# tACS_precision_revised.net
KiCad netlist of a schematic drawn in EAGLE
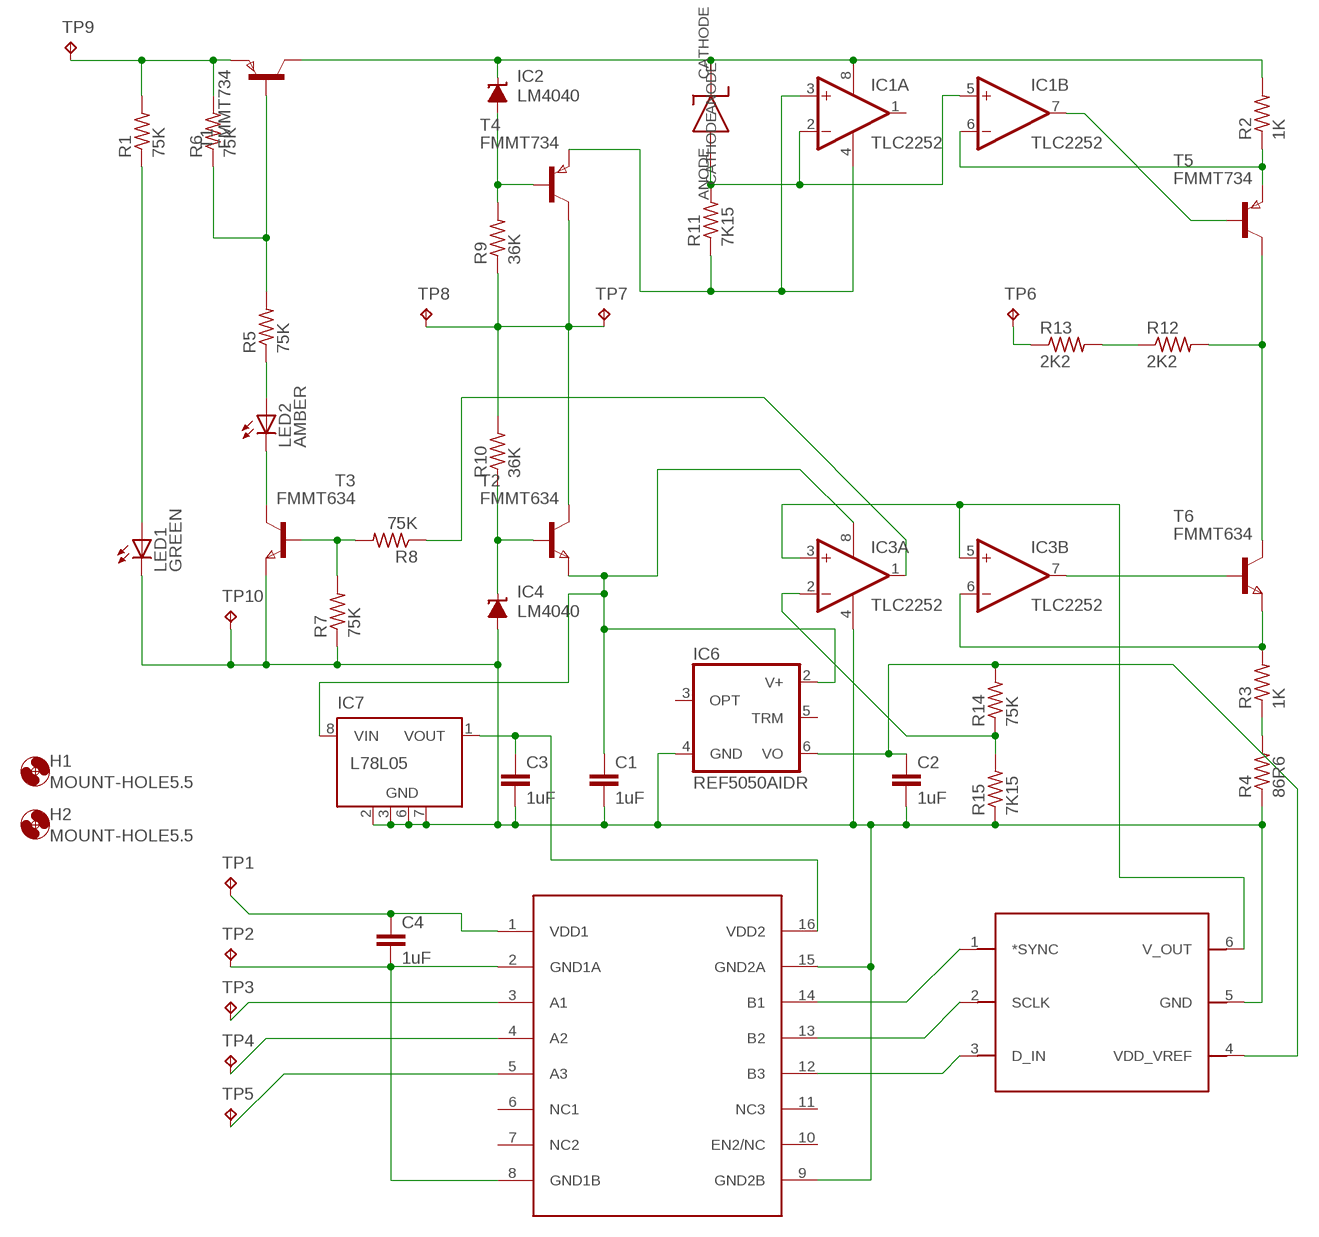
[diagram p0: schematic, sheet 1]

(export (version "E")
  (design (tool "Eeschema 10.0.6"))
  (components
    (comp (ref "C1")
      (value "1uF")
      (footprint "eagle-import:C1608")
      (libsource (lib "eagle-import") (part "C-EUC1608"))
    )
    (comp (ref "C2")
      (value "1uF")
      (footprint "eagle-import:C1608")
      (libsource (lib "eagle-import") (part "C-EUC1608"))
    )
    (comp (ref "C3")
      (value "1uF")
      (footprint "eagle-import:C1608")
      (libsource (lib "eagle-import") (part "C-EUC1608"))
    )
    (comp (ref "C4")
      (value "1uF")
      (footprint "eagle-import:C1608")
      (libsource (lib "eagle-import") (part "C-EUC1608"))
    )
    (comp (ref "H1")
      (value "MOUNT-HOLE5.5")
      (footprint "eagle-import:5,5")
      (libsource (lib "eagle-import") (part "MOUNT-HOLE5.5"))
    )
    (comp (ref "H2")
      (value "MOUNT-HOLE5.5")
      (footprint "eagle-import:5,5")
      (libsource (lib "eagle-import") (part "MOUNT-HOLE5.5"))
    )
    (comp (ref "IC1")
      (value "TLC2252")
      (footprint "eagle-import:SO08")
      (libsource (lib "eagle-import") (part "TLC272D"))
    )
    (comp (ref "IC2")
      (value "LM4040")
      (footprint "eagle-import:DBZ_R-PDSO-G3")
      (fields (field (name "MPN") "LM4041A12IDBZR"))
      (libsource (lib "eagle-import") (part "LM4041DBZA12"))
    )
    (comp (ref "IC3")
      (value "TLC2252")
      (footprint "eagle-import:SO08")
      (libsource (lib "eagle-import") (part "TLC272D"))
    )
    (comp (ref "IC4")
      (value "LM4040")
      (footprint "eagle-import:DBZ_R-PDSO-G3")
      (fields (field (name "MPN") "LM4041A12IDBZR"))
      (libsource (lib "eagle-import") (part "LM4041DBZA12"))
    )
    (comp (ref "IC6")
      (value "REF5050AIDR")
      (footprint "eagle-import:SO08")
      (libsource (lib "eagle-import") (part "REF03D"))
    )
    (comp (ref "IC7")
      (value "L78L05")
      (footprint "eagle-import:SO08")
      (libsource (lib "eagle-import") (part "78LSMD05"))
    )
    (comp (ref "LED1")
      (value "GREEN")
      (footprint "eagle-import:SML0603")
      (libsource (lib "eagle-import") (part "LEDSML0603"))
    )
    (comp (ref "LED2")
      (value "AMBER")
      (footprint "eagle-import:SML1206")
      (libsource (lib "eagle-import") (part "LEDSML1206"))
    )
    (comp (ref "R1")
      (value "75K")
      (footprint "eagle-import:R0603")
      (libsource (lib "eagle-import") (part "R-US_R0603"))
    )
    (comp (ref "R2")
      (value "1K")
      (footprint "eagle-import:R0603")
      (libsource (lib "eagle-import") (part "R-US_R0603"))
    )
    (comp (ref "R3")
      (value "1K")
      (footprint "eagle-import:R0603")
      (libsource (lib "eagle-import") (part "R-US_R0603"))
    )
    (comp (ref "R4")
      (value "86R6")
      (footprint "eagle-import:R0603")
      (libsource (lib "eagle-import") (part "R-US_R0603"))
    )
    (comp (ref "R5")
      (value "75K")
      (footprint "eagle-import:R0603")
      (libsource (lib "eagle-import") (part "R-US_R0603"))
    )
    (comp (ref "R6")
      (value "75K")
      (footprint "eagle-import:R0603")
      (libsource (lib "eagle-import") (part "R-US_R0603"))
    )
    (comp (ref "R7")
      (value "75K")
      (footprint "eagle-import:R0603")
      (libsource (lib "eagle-import") (part "R-US_R0603"))
    )
    (comp (ref "R8")
      (value "75K")
      (footprint "eagle-import:R0603")
      (libsource (lib "eagle-import") (part "R-US_R0603"))
    )
    (comp (ref "R9")
      (value "36K")
      (footprint "eagle-import:R0603")
      (libsource (lib "eagle-import") (part "R-US_R0603"))
    )
    (comp (ref "R10")
      (value "36K")
      (footprint "eagle-import:R0603")
      (libsource (lib "eagle-import") (part "R-US_R0603"))
    )
    (comp (ref "R11")
      (value "7K15")
      (footprint "eagle-import:R0603")
      (libsource (lib "eagle-import") (part "R-US_R0603"))
    )
    (comp (ref "R12")
      (value "2K2")
      (footprint "eagle-import:R2512")
      (libsource (lib "eagle-import") (part "R-US_R2512"))
    )
    (comp (ref "R13")
      (value "2K2")
      (footprint "eagle-import:R2512")
      (libsource (lib "eagle-import") (part "R-US_R2512"))
    )
    (comp (ref "R14")
      (value "75K")
      (footprint "eagle-import:R0603")
      (libsource (lib "eagle-import") (part "R-US_R0603"))
    )
    (comp (ref "R15")
      (value "7K15")
      (footprint "eagle-import:R0603")
      (libsource (lib "eagle-import") (part "R-US_R0603"))
    )
    (comp (ref "T1")
      (value "FMMT734")
      (footprint "eagle-import:SOT-23")
      (fields (field (name "MPN") "FMMT720"))
      (libsource (lib "eagle-import") (part "FMMT720"))
    )
    (comp (ref "T2")
      (value "FMMT634")
      (footprint "eagle-import:SOT-23")
      (fields (field (name "MPN") "FMMT619"))
      (libsource (lib "eagle-import") (part "FMMT624"))
    )
    (comp (ref "T3")
      (value "FMMT634")
      (footprint "eagle-import:SOT-23")
      (fields (field (name "MPN") "FMMT619"))
      (libsource (lib "eagle-import") (part "FMMT624"))
    )
    (comp (ref "T4")
      (value "FMMT734")
      (footprint "eagle-import:SOT-23")
      (fields (field (name "MPN") "FMMT720"))
      (libsource (lib "eagle-import") (part "FMMT720"))
    )
    (comp (ref "T5")
      (value "FMMT734")
      (footprint "eagle-import:SOT-23")
      (fields (field (name "MPN") "FMMT720"))
      (libsource (lib "eagle-import") (part "FMMT720"))
    )
    (comp (ref "T6")
      (value "FMMT634")
      (footprint "eagle-import:SOT-23")
      (fields (field (name "MPN") "FMMT619"))
      (libsource (lib "eagle-import") (part "FMMT624"))
    )
    (comp (ref "TP1")
      (value "TPPAD1-13Y")
      (footprint "eagle-import:P1-13Y")
      (libsource (lib "eagle-import") (part "TPPAD1-13Y"))
    )
    (comp (ref "TP2")
      (value "TPPAD1-13Y")
      (footprint "eagle-import:P1-13Y")
      (libsource (lib "eagle-import") (part "TPPAD1-13Y"))
    )
    (comp (ref "TP3")
      (value "TPPAD1-13Y")
      (footprint "eagle-import:P1-13Y")
      (libsource (lib "eagle-import") (part "TPPAD1-13Y"))
    )
    (comp (ref "TP4")
      (value "TPPAD1-13Y")
      (footprint "eagle-import:P1-13Y")
      (libsource (lib "eagle-import") (part "TPPAD1-13Y"))
    )
    (comp (ref "TP5")
      (value "TPPAD1-13Y")
      (footprint "eagle-import:P1-13Y")
      (libsource (lib "eagle-import") (part "TPPAD1-13Y"))
    )
    (comp (ref "TP6")
      (value "TPPAD1-13Y")
      (footprint "eagle-import:P1-13Y")
      (libsource (lib "eagle-import") (part "TPPAD1-13Y"))
    )
    (comp (ref "TP7")
      (value "TPPAD1-13Y")
      (footprint "eagle-import:P1-13Y")
      (libsource (lib "eagle-import") (part "TPPAD1-13Y"))
    )
    (comp (ref "TP8")
      (value "TPPAD1-13Y")
      (footprint "eagle-import:P1-13Y")
      (libsource (lib "eagle-import") (part "TPPAD1-13Y"))
    )
    (comp (ref "TP9")
      (value "TPPAD1-13Y")
      (footprint "eagle-import:P1-13Y")
      (libsource (lib "eagle-import") (part "TPPAD1-13Y"))
    )
    (comp (ref "TP10")
      (value "TPPAD1-13Y")
      (footprint "eagle-import:P1-13Y")
      (libsource (lib "eagle-import") (part "TPPAD1-13Y"))
    )
    (comp (ref "U$1")
      (value "DAC7311")
      (footprint "eagle-import:SC70-6")
      (libsource (lib "eagle-import") (part "DAC7311"))
    )
    (comp (ref "U$2")
      (value "SI8630BD")
      (footprint "eagle-import:SOIC16R")
      (libsource (lib "eagle-import") (part "SI8630BD-B-IS"))
    )
    (comp (ref "U$3")
      (value "ADR5041")
      (footprint "eagle-import:SC70-3")
      (libsource (lib "eagle-import") (part "ADR5041BKSZ"))
    )
  )
  (nets
    (net (code "1") (name "Net-(IC1A-+IN)") (class "Default")
      (node (ref "IC1") (pin "3") (pinfunction "+IN_3") (pintype "input"))
      (node (ref "IC1") (pin "4") (pinfunction "V-_4") (pintype "power_in"))
      (node (ref "R11") (pin "1") (pinfunction "1_1") (pintype "passive"))
      (node (ref "T4") (pin "2") (pinfunction "E_2") (pintype "passive"))
    )
    (net (code "2") (name "Net-(IC1A--IN)") (class "Default")
      (node (ref "IC1") (pin "2") (pinfunction "-IN_2") (pintype "input"))
      (node (ref "IC1") (pin "5") (pinfunction "+IN_5") (pintype "input"))
      (node (ref "R11") (pin "2") (pinfunction "2_2") (pintype "passive"))
      (node (ref "U$3") (pin "ANODE") (pinfunction "ANODE_ANODE") (pintype "bidirectional"))
    )
    (net (code "3") (name "Net-(IC1B--IN)") (class "Default")
      (node (ref "IC1") (pin "6") (pinfunction "-IN_6") (pintype "input"))
      (node (ref "R2") (pin "1") (pinfunction "1_1") (pintype "passive"))
      (node (ref "T5") (pin "2") (pinfunction "E_2") (pintype "passive"))
    )
    (net (code "4") (name "Net-(IC1B-OUT)") (class "Default")
      (node (ref "IC1") (pin "7") (pinfunction "OUT_7") (pintype "output"))
      (node (ref "T5") (pin "3") (pinfunction "B_3") (pintype "passive"))
    )
    (net (code "5") (name "Net-(IC1C-V+)") (class "Default")
      (node (ref "IC1") (pin "8") (pinfunction "V+_8") (pintype "power_in"))
      (node (ref "IC2") (pin "1") (pinfunction "C_1") (pintype "passive"))
      (node (ref "R2") (pin "2") (pinfunction "2_2") (pintype "passive"))
      (node (ref "T1") (pin "1") (pinfunction "C_1") (pintype "passive"))
      (node (ref "U$3") (pin "CATHODE") (pinfunction "CATHODE_CATHODE") (pintype "bidirectional"))
    )
    (net (code "6") (name "Net-(IC2-A)") (class "Default")
      (node (ref "IC2") (pin "2") (pinfunction "A_2") (pintype "passive"))
      (node (ref "R9") (pin "2") (pinfunction "2_2") (pintype "passive"))
      (node (ref "T4") (pin "3") (pinfunction "B_3") (pintype "passive"))
    )
    (net (code "7") (name "Net-(IC3A-+IN)") (class "Default")
      (node (ref "IC3") (pin "3") (pinfunction "+IN_3") (pintype "input"))
      (node (ref "IC3") (pin "5") (pinfunction "+IN_5") (pintype "input"))
      (node (ref "U$1") (pin "6") (pinfunction "V_OUT_6") (pintype "bidirectional"))
    )
    (net (code "8") (name "Net-(IC3A--IN)") (class "Default")
      (node (ref "IC3") (pin "2") (pinfunction "-IN_2") (pintype "input"))
      (node (ref "R14") (pin "1") (pinfunction "1_1") (pintype "passive"))
      (node (ref "R15") (pin "2") (pinfunction "2_2") (pintype "passive"))
    )
    (net (code "9") (name "Net-(IC3A-OUT)") (class "Default")
      (node (ref "IC3") (pin "1") (pinfunction "OUT_1") (pintype "output"))
      (node (ref "R8") (pin "1") (pinfunction "1_1") (pintype "passive"))
    )
    (net (code "10") (name "Net-(IC3B--IN)") (class "Default")
      (node (ref "IC3") (pin "6") (pinfunction "-IN_6") (pintype "input"))
      (node (ref "R3") (pin "2") (pinfunction "2_2") (pintype "passive"))
      (node (ref "T6") (pin "2") (pinfunction "E_2") (pintype "passive"))
    )
    (net (code "11") (name "Net-(IC3B-OUT)") (class "Default")
      (node (ref "IC3") (pin "7") (pinfunction "OUT_7") (pintype "output"))
      (node (ref "T6") (pin "3") (pinfunction "B_3") (pintype "passive"))
    )
    (net (code "12") (name "Net-(IC3C-V+)") (class "Default")
      (node (ref "C1") (pin "1") (pinfunction "1_1") (pintype "passive"))
      (node (ref "IC3") (pin "8") (pinfunction "V+_8") (pintype "power_in"))
      (node (ref "IC6") (pin "2") (pinfunction "V+_2") (pintype "power_in"))
      (node (ref "IC7") (pin "8") (pinfunction "VIN_8") (pintype "passive"))
      (node (ref "T2") (pin "2") (pinfunction "E_2") (pintype "passive"))
    )
    (net (code "13") (name "Net-(IC3C-V-)") (class "Default")
      (node (ref "C1") (pin "2") (pinfunction "2_2") (pintype "passive"))
      (node (ref "C2") (pin "2") (pinfunction "2_2") (pintype "passive"))
      (node (ref "C3") (pin "2") (pinfunction "2_2") (pintype "passive"))
      (node (ref "IC3") (pin "4") (pinfunction "V-_4") (pintype "power_in"))
      (node (ref "IC4") (pin "2") (pinfunction "A_2") (pintype "passive"))
      (node (ref "IC6") (pin "4") (pinfunction "GND_4") (pintype "power_in"))
      (node (ref "IC7") (pin "2") (pinfunction "GND_2") (pintype "power_in"))
      (node (ref "IC7") (pin "3") (pinfunction "GND_3") (pintype "power_in"))
      (node (ref "IC7") (pin "6") (pinfunction "GND_6") (pintype "power_in"))
      (node (ref "IC7") (pin "7") (pinfunction "GND_7") (pintype "power_in"))
      (node (ref "LED1") (pin "C") (pinfunction "C_C") (pintype "passive"))
      (node (ref "R15") (pin "1") (pinfunction "1_1") (pintype "passive"))
      (node (ref "R4") (pin "1") (pinfunction "1_1") (pintype "passive"))
      (node (ref "R7") (pin "1") (pinfunction "1_1") (pintype "passive"))
      (node (ref "T3") (pin "2") (pinfunction "E_2") (pintype "passive"))
      (node (ref "TP10") (pin "TP") (pinfunction "TP_TP") (pintype "input"))
      (node (ref "U$1") (pin "5") (pinfunction "GND_5") (pintype "bidirectional"))
      (node (ref "U$2") (pin "15") (pinfunction "GND2A_15") (pintype "bidirectional"))
      (node (ref "U$2") (pin "9") (pinfunction "GND2B_9") (pintype "bidirectional"))
    )
    (net (code "14") (name "Net-(IC4-C)") (class "Default")
      (node (ref "IC4") (pin "1") (pinfunction "C_1") (pintype "passive"))
      (node (ref "R10") (pin "1") (pinfunction "1_1") (pintype "passive"))
      (node (ref "T2") (pin "3") (pinfunction "B_3") (pintype "passive"))
    )
    (net (code "15") (name "Net-(IC6-VO)") (class "Default")
      (node (ref "C2") (pin "1") (pinfunction "1_1") (pintype "passive"))
      (node (ref "IC6") (pin "6") (pinfunction "VO_6") (pintype "output"))
      (node (ref "R14") (pin "2") (pinfunction "2_2") (pintype "passive"))
      (node (ref "U$1") (pin "4") (pinfunction "VDD_VREF_4") (pintype "bidirectional"))
    )
    (net (code "16") (name "Net-(IC7A-VOUT)") (class "Default")
      (node (ref "C3") (pin "1") (pinfunction "1_1") (pintype "passive"))
      (node (ref "IC7") (pin "1") (pinfunction "VOUT_1") (pintype "output"))
      (node (ref "U$2") (pin "16") (pinfunction "VDD2_16") (pintype "bidirectional"))
    )
    (net (code "17") (name "Net-(LED1-PadA)") (class "Default")
      (node (ref "LED1") (pin "A") (pinfunction "A_A") (pintype "passive"))
      (node (ref "R1") (pin "1") (pinfunction "1_1") (pintype "passive"))
    )
    (net (code "18") (name "Net-(LED2-PadA)") (class "Default")
      (node (ref "LED2") (pin "A") (pinfunction "A_A") (pintype "passive"))
      (node (ref "R5") (pin "1") (pinfunction "1_1") (pintype "passive"))
    )
    (net (code "19") (name "Net-(R3-Pad1)") (class "Default")
      (node (ref "R3") (pin "1") (pinfunction "1_1") (pintype "passive"))
      (node (ref "R4") (pin "2") (pinfunction "2_2") (pintype "passive"))
    )
    (net (code "20") (name "Net-(R12-Pad1)") (class "Default")
      (node (ref "R12") (pin "1") (pinfunction "1_1") (pintype "passive"))
      (node (ref "R13") (pin "2") (pinfunction "2_2") (pintype "passive"))
    )
    (net (code "21") (name "Net-(R13-Pad1)") (class "Default")
      (node (ref "R13") (pin "1") (pinfunction "1_1") (pintype "passive"))
      (node (ref "TP6") (pin "TP") (pinfunction "TP_TP") (pintype "input"))
    )
    (net (code "22") (name "Net-(T1-B)") (class "Default")
      (node (ref "R5") (pin "2") (pinfunction "2_2") (pintype "passive"))
      (node (ref "R6") (pin "1") (pinfunction "1_1") (pintype "passive"))
      (node (ref "T1") (pin "3") (pinfunction "B_3") (pintype "passive"))
    )
    (net (code "23") (name "Net-(T1-E)") (class "Default")
      (node (ref "R1") (pin "2") (pinfunction "2_2") (pintype "passive"))
      (node (ref "R6") (pin "2") (pinfunction "2_2") (pintype "passive"))
      (node (ref "T1") (pin "2") (pinfunction "E_2") (pintype "passive"))
      (node (ref "TP9") (pin "TP") (pinfunction "TP_TP") (pintype "input"))
    )
    (net (code "24") (name "Net-(T2-C)") (class "Default")
      (node (ref "R10") (pin "2") (pinfunction "2_2") (pintype "passive"))
      (node (ref "R9") (pin "1") (pinfunction "1_1") (pintype "passive"))
      (node (ref "T2") (pin "1") (pinfunction "C_1") (pintype "passive"))
      (node (ref "T4") (pin "1") (pinfunction "C_1") (pintype "passive"))
      (node (ref "TP7") (pin "TP") (pinfunction "TP_TP") (pintype "input"))
      (node (ref "TP8") (pin "TP") (pinfunction "TP_TP") (pintype "input"))
    )
    (net (code "25") (name "Net-(T3-B)") (class "Default")
      (node (ref "R7") (pin "2") (pinfunction "2_2") (pintype "passive"))
      (node (ref "R8") (pin "2") (pinfunction "2_2") (pintype "passive"))
      (node (ref "T3") (pin "3") (pinfunction "B_3") (pintype "passive"))
    )
    (net (code "26") (name "Net-(T3-C)") (class "Default")
      (node (ref "LED2") (pin "C") (pinfunction "C_C") (pintype "passive"))
      (node (ref "T3") (pin "1") (pinfunction "C_1") (pintype "passive"))
    )
    (net (code "27") (name "Net-(T5-C)") (class "Default")
      (node (ref "R12") (pin "2") (pinfunction "2_2") (pintype "passive"))
      (node (ref "T5") (pin "1") (pinfunction "C_1") (pintype "passive"))
      (node (ref "T6") (pin "1") (pinfunction "C_1") (pintype "passive"))
    )
    (net (code "28") (name "Net-(U$1-*SYNC)") (class "Default")
      (node (ref "U$1") (pin "1") (pinfunction "*SYNC_1") (pintype "bidirectional"))
      (node (ref "U$2") (pin "14") (pinfunction "B1_14") (pintype "bidirectional"))
    )
    (net (code "29") (name "Net-(U$1-D_IN)") (class "Default")
      (node (ref "U$1") (pin "3") (pinfunction "D_IN_3") (pintype "bidirectional"))
      (node (ref "U$2") (pin "12") (pinfunction "B3_12") (pintype "bidirectional"))
    )
    (net (code "30") (name "Net-(U$1-SCLK)") (class "Default")
      (node (ref "U$1") (pin "2") (pinfunction "SCLK_2") (pintype "bidirectional"))
      (node (ref "U$2") (pin "13") (pinfunction "B2_13") (pintype "bidirectional"))
    )
    (net (code "31") (name "Net-(U$2-A1)") (class "Default")
      (node (ref "TP3") (pin "TP") (pinfunction "TP_TP") (pintype "input"))
      (node (ref "U$2") (pin "3") (pinfunction "A1_3") (pintype "bidirectional"))
    )
    (net (code "32") (name "Net-(U$2-A2)") (class "Default")
      (node (ref "TP4") (pin "TP") (pinfunction "TP_TP") (pintype "input"))
      (node (ref "U$2") (pin "4") (pinfunction "A2_4") (pintype "bidirectional"))
    )
    (net (code "33") (name "Net-(U$2-A3)") (class "Default")
      (node (ref "TP5") (pin "TP") (pinfunction "TP_TP") (pintype "input"))
      (node (ref "U$2") (pin "5") (pinfunction "A3_5") (pintype "bidirectional"))
    )
    (net (code "34") (name "Net-(U$2-GND1A)") (class "Default")
      (node (ref "C4") (pin "2") (pinfunction "2_2") (pintype "passive"))
      (node (ref "TP2") (pin "TP") (pinfunction "TP_TP") (pintype "input"))
      (node (ref "U$2") (pin "2") (pinfunction "GND1A_2") (pintype "bidirectional"))
      (node (ref "U$2") (pin "8") (pinfunction "GND1B_8") (pintype "bidirectional"))
    )
    (net (code "35") (name "Net-(U$2-VDD1)") (class "Default")
      (node (ref "C4") (pin "1") (pinfunction "1_1") (pintype "passive"))
      (node (ref "TP1") (pin "TP") (pinfunction "TP_TP") (pintype "input"))
      (node (ref "U$2") (pin "1") (pinfunction "VDD1_1") (pintype "bidirectional"))
    )
    (net (code "36") (name "unconnected-(IC1A-OUT-Pad1)") (class "Default")
      (node (ref "IC1") (pin "1") (pinfunction "OUT_1") (pintype "output"))
    )
    (net (code "37") (name "unconnected-(IC6-OPT-Pad3)") (class "Default")
      (node (ref "IC6") (pin "3") (pinfunction "OPT_3") (pintype "output"))
    )
    (net (code "38") (name "unconnected-(IC6-TRM-Pad5)") (class "Default")
      (node (ref "IC6") (pin "5") (pinfunction "TRM_5") (pintype "input"))
    )
    (net (code "39") (name "unconnected-(U$2-EN2{slash}NC-Pad10)") (class "Default")
      (node (ref "U$2") (pin "10") (pinfunction "EN2/NC_10") (pintype "bidirectional"))
    )
    (net (code "40") (name "unconnected-(U$2-NC1-Pad6)") (class "Default")
      (node (ref "U$2") (pin "6") (pinfunction "NC1_6") (pintype "bidirectional"))
    )
    (net (code "41") (name "unconnected-(U$2-NC2-Pad7)") (class "Default")
      (node (ref "U$2") (pin "7") (pinfunction "NC2_7") (pintype "bidirectional"))
    )
    (net (code "42") (name "unconnected-(U$2-NC3-Pad11)") (class "Default")
      (node (ref "U$2") (pin "11") (pinfunction "NC3_11") (pintype "bidirectional"))
    )
  )
)
